# 7_VGA.net
KiCad netlist of a schematic drawn in Altium Designer
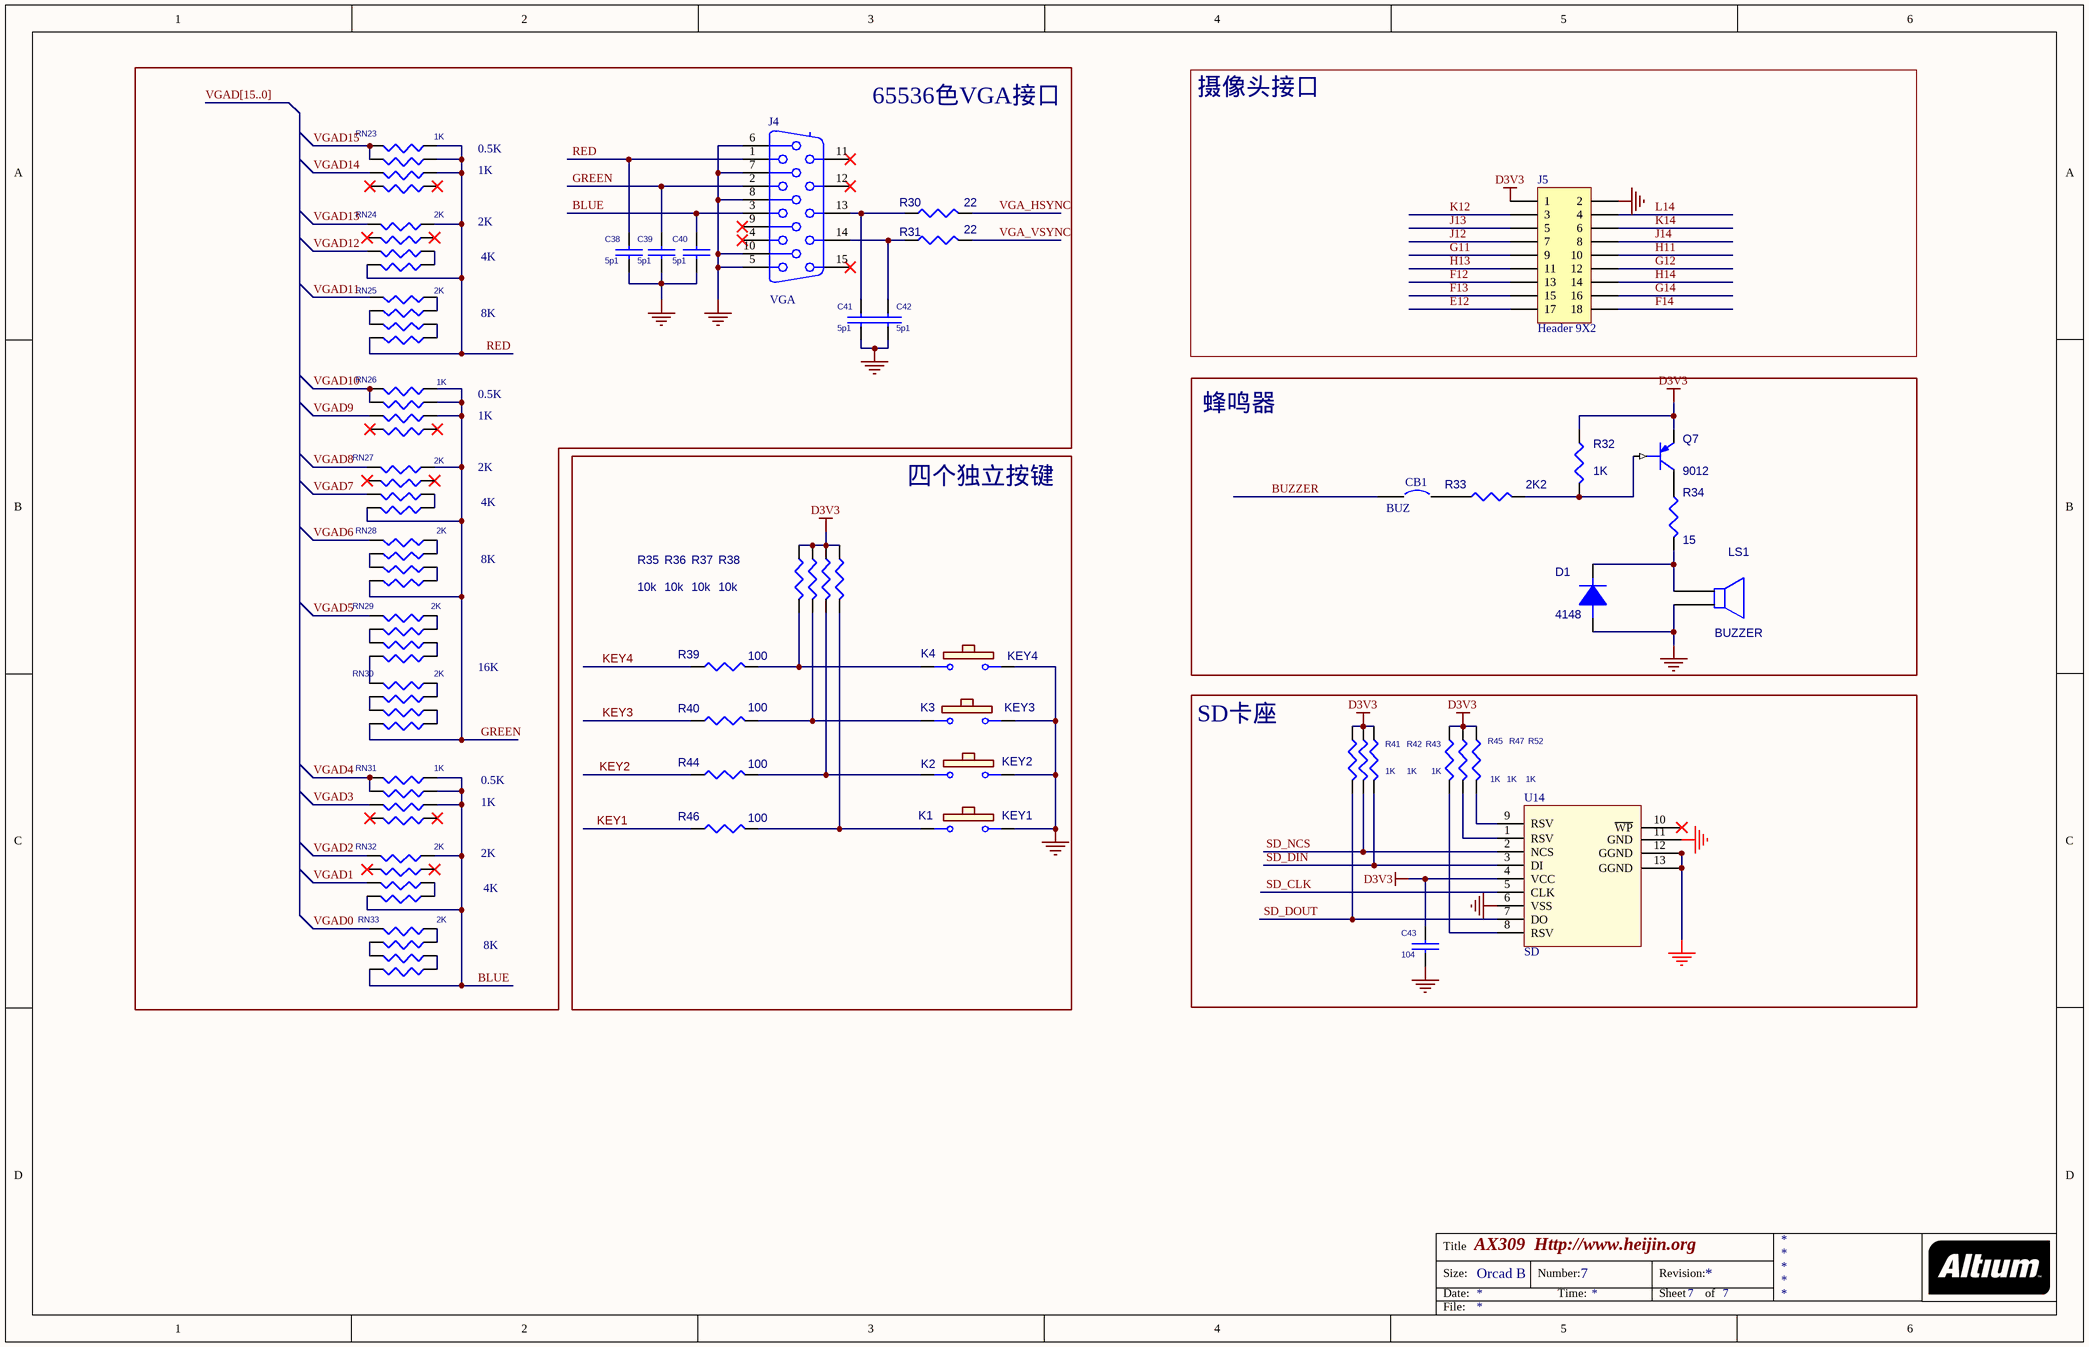
[diagram p0: 7_VGA.SchDoc]

(export (version "E")
  (design (tool "Eeschema 10.0.6"))
  (components
    (comp (ref "C38") (value "5p1") (footprint "0603") (libsource (lib "*") (part "C_Dup1")))
    (comp (ref "C39") (value "5p1") (footprint "0603") (libsource (lib "*") (part "C_Dup1")))
    (comp (ref "C40") (value "5p1") (footprint "0603") (libsource (lib "*") (part "C_Dup1")))
    (comp (ref "C41") (value "5p1") (footprint "0603") (libsource (lib "*") (part "C_Dup1")))
    (comp (ref "C42") (value "5p1") (footprint "0603") (libsource (lib "*") (part "C_Dup1")))
    (comp (ref "C43") (value "104") (footprint "0402") (libsource (lib "*") (part "C_Dup1")))
    (comp (ref "CB1")
      (value "BUZ")
      (footprint "SIP2")
      (description "Circuit Breaker")
      (fields (field (name "PUBLISHER") "Altium Limited"))
      (libsource (lib "Miscellaneous Devices") (part "Circuit Breaker"))
    )
    (comp (ref "D1") (value "4148") (libsource (lib "*") (part "4148")))
    (comp (ref "J4")
      (value "VGA")
      (footprint "wfj_pcb:VGA")
      (description "Receptacle Assembly, 15-Pin, Sim Line Connector")
      (fields (field (name "PUBLISHER") "Altium Limited"))
      (libsource (lib "Miscellaneous Connectors") (part "Connector 15"))
    )
    (comp (ref "J5")
      (value "Header 9X2")
      (footprint "HDR2X9")
      (description "Header, 9-Pin, Dual row")
      (fields (field (name "PUBLISHER") "Altium Limited"))
      (libsource (lib "Miscellaneous Connectors") (part "Header 9X2"))
    )
    (comp (ref "K1") (value "KEY1") (footprint "KEY735SO") (libsource (lib "*") (part "KEYB")))
    (comp (ref "K2") (value "KEY2") (footprint "KEY735SO") (libsource (lib "*") (part "KEYB")))
    (comp (ref "K3") (value "KEY3") (footprint "KEY735SO") (libsource (lib "") (part "KEYB_1")))
    (comp (ref "K4") (value "KEY4") (footprint "KEY735SO") (libsource (lib "*") (part "KEYB")))
    (comp (ref "LS1") (value "BUZZER") (libsource (lib "*") (part "SPEAKER")))
    (comp (ref "Q7") (value "9012") (footprint "SOT23") (libsource (lib "*") (part "PNP")))
    (comp (ref "R30") (value "22") (footprint "0603") (libsource (lib "*") (part "R")))
    (comp (ref "R31") (value "22") (footprint "0603") (libsource (lib "*") (part "R")))
    (comp (ref "R32") (value "1K") (footprint "0603") (libsource (lib "*") (part "R_Dup3")))
    (comp (ref "R33") (value "2K2") (footprint "0603") (libsource (lib "*") (part "R_Dup3")))
    (comp (ref "R34") (value "15") (footprint "0603") (libsource (lib "*") (part "R_Dup3")))
    (comp (ref "R35") (value "10k") (footprint "0603") (libsource (lib "*") (part "R_Dup2")))
    (comp (ref "R36") (value "10k") (footprint "0603") (libsource (lib "*") (part "R_Dup2")))
    (comp (ref "R37") (value "10k") (footprint "0603") (libsource (lib "*") (part "R_Dup2")))
    (comp (ref "R38") (value "10k") (footprint "0603") (libsource (lib "*") (part "R_Dup2")))
    (comp (ref "R39") (value "100") (footprint "0603") (libsource (lib "*") (part "R_Dup2")))
    (comp (ref "R40") (value "100") (footprint "0603") (libsource (lib "*") (part "R_Dup2")))
    (comp (ref "R41") (value "1K") (footprint "0603") (libsource (lib "*") (part "R")))
    (comp (ref "R42") (value "1K") (footprint "0603") (libsource (lib "*") (part "R")))
    (comp (ref "R43") (value "1K") (footprint "0603") (libsource (lib "*") (part "R")))
    (comp (ref "R44") (value "100") (footprint "0603") (libsource (lib "*") (part "R_Dup2")))
    (comp (ref "R45") (value "1K") (footprint "0603") (libsource (lib "*") (part "R")))
    (comp (ref "R46") (value "100") (footprint "0603") (libsource (lib "*") (part "R_Dup2")))
    (comp (ref "R47") (value "1K") (footprint "0603") (libsource (lib "*") (part "R")))
    (comp (ref "R52") (value "1K") (footprint "0603") (libsource (lib "*") (part "R")))
    (comp (ref "RN23") (value "1K") (footprint "RN-8P") (libsource (lib "*") (part "RN_Dup1")))
    (comp (ref "RN24") (value "2K") (footprint "RN-8P") (libsource (lib "*") (part "RN_Dup1")))
    (comp (ref "RN25") (value "2K") (footprint "RN-8P") (libsource (lib "*") (part "RN_Dup1")))
    (comp (ref "RN26") (value "1K") (footprint "RN-8P") (libsource (lib "*") (part "RN_Dup1")))
    (comp (ref "RN27") (value "2K") (footprint "RN-8P") (libsource (lib "*") (part "RN_Dup1")))
    (comp (ref "RN28") (value "2K") (footprint "RN-8P") (libsource (lib "*") (part "RN_Dup1")))
    (comp (ref "RN29") (value "2K") (footprint "RN-8P") (libsource (lib "*") (part "RN_Dup1")))
    (comp (ref "RN30") (value "2K") (footprint "RN-8P") (libsource (lib "*") (part "RN_Dup1")))
    (comp (ref "RN31") (value "1K") (footprint "RN-8P") (libsource (lib "*") (part "RN_Dup1")))
    (comp (ref "RN32") (value "2K") (footprint "RN-8P") (libsource (lib "*") (part "RN_Dup1")))
    (comp (ref "RN33") (value "2K") (footprint "RN-8P") (libsource (lib "*") (part "RN_Dup1")))
    (comp (ref "U14") (value "SD") (footprint "TF") (libsource (lib "TFT") (part "SD")))
  )
  (nets
    (net (code "1") (name "/BLUE") (class "Default")
      (node (ref "C40") (pin "1") (pinfunction "1_1") (pintype "passive"))
      (node (ref "J4") (pin "3") (pinfunction "3_3") (pintype "passive"))
      (node (ref "RN31") (pin "2") (pinfunction "2_2") (pintype "passive"))
      (node (ref "RN31") (pin "3") (pinfunction "3_3") (pintype "passive"))
      (node (ref "RN31") (pin "4") (pinfunction "4_4") (pintype "passive"))
      (node (ref "RN32") (pin "4") (pinfunction "4_4") (pintype "passive"))
      (node (ref "RN32") (pin "8") (pinfunction "8_8") (pintype "passive"))
      (node (ref "RN33") (pin "8") (pinfunction "8_8") (pintype "passive"))
    )
    (net (code "2") (name "/BUZZER") (class "Default")
      (node (ref "CB1") (pin "1") (pinfunction "1_1") (pintype "passive"))
    )
    (net (code "3") (name "/E12") (class "Default")
      (node (ref "J5") (pin "17") (pinfunction "17_17") (pintype "passive"))
    )
    (net (code "4") (name "/F12") (class "Default")
      (node (ref "J5") (pin "13") (pinfunction "13_13") (pintype "passive"))
    )
    (net (code "5") (name "/F13") (class "Default")
      (node (ref "J5") (pin "15") (pinfunction "15_15") (pintype "passive"))
    )
    (net (code "6") (name "/F14") (class "Default")
      (node (ref "J5") (pin "18") (pinfunction "18_18") (pintype "passive"))
    )
    (net (code "7") (name "/G11") (class "Default")
      (node (ref "J5") (pin "9") (pinfunction "9_9") (pintype "passive"))
    )
    (net (code "8") (name "/G12") (class "Default")
      (node (ref "J5") (pin "12") (pinfunction "12_12") (pintype "passive"))
    )
    (net (code "9") (name "/G14") (class "Default")
      (node (ref "J5") (pin "16") (pinfunction "16_16") (pintype "passive"))
    )
    (net (code "10") (name "/GREEN") (class "Default")
      (node (ref "C39") (pin "1") (pinfunction "1_1") (pintype "passive"))
      (node (ref "J4") (pin "2") (pinfunction "2_2") (pintype "passive"))
      (node (ref "RN26") (pin "2") (pinfunction "2_2") (pintype "passive"))
      (node (ref "RN26") (pin "3") (pinfunction "3_3") (pintype "passive"))
      (node (ref "RN26") (pin "4") (pinfunction "4_4") (pintype "passive"))
      (node (ref "RN27") (pin "4") (pinfunction "4_4") (pintype "passive"))
      (node (ref "RN27") (pin "8") (pinfunction "8_8") (pintype "passive"))
      (node (ref "RN28") (pin "8") (pinfunction "8_8") (pintype "passive"))
      (node (ref "RN30") (pin "8") (pinfunction "8_8") (pintype "passive"))
    )
    (net (code "11") (name "/H11") (class "Default")
      (node (ref "J5") (pin "10") (pinfunction "10_10") (pintype "passive"))
    )
    (net (code "12") (name "/H13") (class "Default")
      (node (ref "J5") (pin "11") (pinfunction "11_11") (pintype "passive"))
    )
    (net (code "13") (name "/H14") (class "Default")
      (node (ref "J5") (pin "14") (pinfunction "14_14") (pintype "passive"))
    )
    (net (code "14") (name "/J12") (class "Default")
      (node (ref "J5") (pin "7") (pinfunction "7_7") (pintype "passive"))
    )
    (net (code "15") (name "/J13") (class "Default")
      (node (ref "J5") (pin "5") (pinfunction "5_5") (pintype "passive"))
    )
    (net (code "16") (name "/J14") (class "Default")
      (node (ref "J5") (pin "8") (pinfunction "8_8") (pintype "passive"))
    )
    (net (code "17") (name "/K12") (class "Default")
      (node (ref "J5") (pin "3") (pinfunction "3_3") (pintype "passive"))
    )
    (net (code "18") (name "/K14") (class "Default")
      (node (ref "J5") (pin "6") (pinfunction "6_6") (pintype "passive"))
    )
    (net (code "19") (name "/KEY1") (class "Default")
      (node (ref "R46") (pin "1") (pinfunction "1_1") (pintype "passive"))
    )
    (net (code "20") (name "/KEY2") (class "Default")
      (node (ref "R44") (pin "1") (pinfunction "1_1") (pintype "passive"))
    )
    (net (code "21") (name "/KEY3") (class "Default")
      (node (ref "R40") (pin "1") (pinfunction "1_1") (pintype "passive"))
    )
    (net (code "22") (name "/KEY4") (class "Default")
      (node (ref "R39") (pin "1") (pinfunction "1_1") (pintype "passive"))
    )
    (net (code "23") (name "/L14") (class "Default")
      (node (ref "J5") (pin "4") (pinfunction "4_4") (pintype "passive"))
    )
    (net (code "24") (name "/RED") (class "Default")
      (node (ref "C38") (pin "1") (pinfunction "1_1") (pintype "passive"))
      (node (ref "J4") (pin "1") (pinfunction "1_1") (pintype "passive"))
      (node (ref "RN23") (pin "2") (pinfunction "2_2") (pintype "passive"))
      (node (ref "RN23") (pin "3") (pinfunction "3_3") (pintype "passive"))
      (node (ref "RN23") (pin "4") (pinfunction "4_4") (pintype "passive"))
      (node (ref "RN24") (pin "4") (pinfunction "4_4") (pintype "passive"))
      (node (ref "RN24") (pin "8") (pinfunction "8_8") (pintype "passive"))
      (node (ref "RN25") (pin "8") (pinfunction "8_8") (pintype "passive"))
    )
    (net (code "25") (name "/SD_CLK") (class "Default")
      (node (ref "U14") (pin "5") (pinfunction "CLK_5") (pintype "passive"))
    )
    (net (code "26") (name "/SD_DIN") (class "Default")
      (node (ref "R43") (pin "2") (pinfunction "2_2") (pintype "passive"))
      (node (ref "U14") (pin "3") (pinfunction "DI_3") (pintype "passive"))
    )
    (net (code "27") (name "/SD_DOUT") (class "Default")
      (node (ref "R41") (pin "2") (pinfunction "2_2") (pintype "passive"))
      (node (ref "U14") (pin "7") (pinfunction "DO_7") (pintype "passive"))
    )
    (net (code "28") (name "/SD_NCS") (class "Default")
      (node (ref "R42") (pin "2") (pinfunction "2_2") (pintype "passive"))
      (node (ref "U14") (pin "2") (pinfunction "NCS_2") (pintype "passive"))
    )
    (net (code "29") (name "/VGAD0") (class "Default")
      (node (ref "RN33") (pin "5") (pinfunction "5_5") (pintype "passive"))
    )
    (net (code "30") (name "/VGAD1") (class "Default")
      (node (ref "RN32") (pin "7") (pinfunction "7_7") (pintype "passive"))
    )
    (net (code "31") (name "/VGAD2") (class "Default")
      (node (ref "RN32") (pin "5") (pinfunction "5_5") (pintype "passive"))
    )
    (net (code "32") (name "/VGAD3") (class "Default")
      (node (ref "RN31") (pin "7") (pinfunction "7_7") (pintype "passive"))
    )
    (net (code "33") (name "/VGAD4") (class "Default")
      (node (ref "RN31") (pin "5") (pinfunction "5_5") (pintype "passive"))
      (node (ref "RN31") (pin "6") (pinfunction "6_6") (pintype "passive"))
    )
    (net (code "34") (name "/VGAD5") (class "Default")
      (node (ref "RN29") (pin "5") (pinfunction "5_5") (pintype "passive"))
    )
    (net (code "35") (name "/VGAD6") (class "Default")
      (node (ref "RN28") (pin "5") (pinfunction "5_5") (pintype "passive"))
    )
    (net (code "36") (name "/VGAD7") (class "Default")
      (node (ref "RN27") (pin "7") (pinfunction "7_7") (pintype "passive"))
    )
    (net (code "37") (name "/VGAD8") (class "Default")
      (node (ref "RN27") (pin "5") (pinfunction "5_5") (pintype "passive"))
    )
    (net (code "38") (name "/VGAD9") (class "Default")
      (node (ref "RN26") (pin "7") (pinfunction "7_7") (pintype "passive"))
    )
    (net (code "39") (name "/VGAD10") (class "Default")
      (node (ref "RN26") (pin "5") (pinfunction "5_5") (pintype "passive"))
      (node (ref "RN26") (pin "6") (pinfunction "6_6") (pintype "passive"))
    )
    (net (code "40") (name "/VGAD11") (class "Default")
      (node (ref "RN25") (pin "5") (pinfunction "5_5") (pintype "passive"))
    )
    (net (code "41") (name "/VGAD12") (class "Default")
      (node (ref "RN24") (pin "7") (pinfunction "7_7") (pintype "passive"))
    )
    (net (code "42") (name "/VGAD13") (class "Default")
      (node (ref "RN24") (pin "5") (pinfunction "5_5") (pintype "passive"))
    )
    (net (code "43") (name "/VGAD14") (class "Default")
      (node (ref "RN23") (pin "7") (pinfunction "7_7") (pintype "passive"))
    )
    (net (code "44") (name "/VGAD15") (class "Default")
      (node (ref "RN23") (pin "5") (pinfunction "5_5") (pintype "passive"))
      (node (ref "RN23") (pin "6") (pinfunction "6_6") (pintype "passive"))
    )
    (net (code "46") (name "/VGA_HSYNC") (class "Default")
      (node (ref "R30") (pin "2") (pinfunction "2_2") (pintype "passive"))
    )
    (net (code "47") (name "/VGA_VSYNC") (class "Default")
      (node (ref "R31") (pin "2") (pinfunction "2_2") (pintype "passive"))
    )
    (net (code "48") (name "D3V3") (class "Default")
      (node (ref "C43") (pin "1") (pinfunction "1_1") (pintype "passive"))
      (node (ref "J5") (pin "1") (pinfunction "1_1") (pintype "passive"))
      (node (ref "Q7") (pin "2") (pinfunction "EMITTER_2") (pintype "passive"))
      (node (ref "R32") (pin "1") (pinfunction "1_1") (pintype "passive"))
      (node (ref "R35") (pin "1") (pinfunction "1_1") (pintype "passive"))
      (node (ref "R36") (pin "1") (pinfunction "1_1") (pintype "passive"))
      (node (ref "R37") (pin "1") (pinfunction "1_1") (pintype "passive"))
      (node (ref "R38") (pin "1") (pinfunction "1_1") (pintype "passive"))
      (node (ref "R41") (pin "1") (pinfunction "1_1") (pintype "passive"))
      (node (ref "R42") (pin "1") (pinfunction "1_1") (pintype "passive"))
      (node (ref "R43") (pin "1") (pinfunction "1_1") (pintype "passive"))
      (node (ref "R45") (pin "1") (pinfunction "1_1") (pintype "passive"))
      (node (ref "R47") (pin "1") (pinfunction "1_1") (pintype "passive"))
      (node (ref "R52") (pin "1") (pinfunction "1_1") (pintype "passive"))
      (node (ref "U14") (pin "4") (pinfunction "VCC_4") (pintype "passive"))
    )
    (net (code "49") (name "GND") (class "Default")
      (node (ref "C38") (pin "2") (pinfunction "2_2") (pintype "passive"))
      (node (ref "C39") (pin "2") (pinfunction "2_2") (pintype "passive"))
      (node (ref "C40") (pin "2") (pinfunction "2_2") (pintype "passive"))
      (node (ref "C41") (pin "2") (pinfunction "2_2") (pintype "passive"))
      (node (ref "C42") (pin "2") (pinfunction "2_2") (pintype "passive"))
      (node (ref "C43") (pin "2") (pinfunction "2_2") (pintype "passive"))
      (node (ref "D1") (pin "1") (pinfunction "A_1") (pintype "passive"))
      (node (ref "J4") (pin "10") (pinfunction "10_10") (pintype "passive"))
      (node (ref "J4") (pin "5") (pinfunction "5_5") (pintype "passive"))
      (node (ref "J4") (pin "6") (pinfunction "6_6") (pintype "passive"))
      (node (ref "J4") (pin "7") (pinfunction "7_7") (pintype "passive"))
      (node (ref "J4") (pin "8") (pinfunction "8_8") (pintype "passive"))
      (node (ref "J5") (pin "2") (pinfunction "2_2") (pintype "passive"))
      (node (ref "K1") (pin "2") (pinfunction "2_2") (pintype "passive"))
      (node (ref "K2") (pin "2") (pinfunction "2_2") (pintype "passive"))
      (node (ref "K3") (pin "1") (pinfunction "1_1") (pintype "passive"))
      (node (ref "K4") (pin "2") (pinfunction "2_2") (pintype "passive"))
      (node (ref "LS1") (pin "2") (pinfunction "2_2") (pintype "passive"))
      (node (ref "U14") (pin "11") (pinfunction "GND_11") (pintype "passive"))
      (node (ref "U14") (pin "12") (pinfunction "GGND_12") (pintype "passive"))
      (node (ref "U14") (pin "13") (pinfunction "GGND_13") (pintype "passive"))
      (node (ref "U14") (pin "6") (pinfunction "VSS_6") (pintype "passive"))
    )
    (net (code "50") (name "Net-(C41-Pad1)") (class "Default")
      (node (ref "C41") (pin "1") (pinfunction "1_1") (pintype "passive"))
      (node (ref "J4") (pin "13") (pinfunction "13_13") (pintype "passive"))
      (node (ref "R30") (pin "1") (pinfunction "1_1") (pintype "passive"))
    )
    (net (code "51") (name "Net-(C42-Pad1)") (class "Default")
      (node (ref "C42") (pin "1") (pinfunction "1_1") (pintype "passive"))
      (node (ref "J4") (pin "14") (pinfunction "14_14") (pintype "passive"))
      (node (ref "R31") (pin "1") (pinfunction "1_1") (pintype "passive"))
    )
    (net (code "52") (name "Net-(CB1-Pad2)") (class "Default")
      (node (ref "CB1") (pin "2") (pinfunction "2_2") (pintype "passive"))
      (node (ref "R33") (pin "1") (pinfunction "1_1") (pintype "passive"))
    )
    (net (code "53") (name "Net-(D1-C)") (class "Default")
      (node (ref "D1") (pin "2") (pinfunction "C_2") (pintype "passive"))
      (node (ref "LS1") (pin "1") (pinfunction "1_1") (pintype "passive"))
      (node (ref "R34") (pin "2") (pinfunction "2_2") (pintype "passive"))
    )
    (net (code "54") (name "Net-(K1-Pad1)") (class "Default")
      (node (ref "K1") (pin "1") (pinfunction "1_1") (pintype "passive"))
      (node (ref "R38") (pin "2") (pinfunction "2_2") (pintype "passive"))
      (node (ref "R46") (pin "2") (pinfunction "2_2") (pintype "passive"))
    )
    (net (code "55") (name "Net-(K2-Pad1)") (class "Default")
      (node (ref "K2") (pin "1") (pinfunction "1_1") (pintype "passive"))
      (node (ref "R37") (pin "2") (pinfunction "2_2") (pintype "passive"))
      (node (ref "R44") (pin "2") (pinfunction "2_2") (pintype "passive"))
    )
    (net (code "56") (name "Net-(K3-Pad2)") (class "Default")
      (node (ref "K3") (pin "2") (pinfunction "2_2") (pintype "passive"))
      (node (ref "R36") (pin "2") (pinfunction "2_2") (pintype "passive"))
      (node (ref "R40") (pin "2") (pinfunction "2_2") (pintype "passive"))
    )
    (net (code "57") (name "Net-(K4-Pad1)") (class "Default")
      (node (ref "K4") (pin "1") (pinfunction "1_1") (pintype "passive"))
      (node (ref "R35") (pin "2") (pinfunction "2_2") (pintype "passive"))
      (node (ref "R39") (pin "2") (pinfunction "2_2") (pintype "passive"))
    )
    (net (code "58") (name "Net-(Q7-BASE)") (class "Default")
      (node (ref "Q7") (pin "1") (pinfunction "BASE_1") (pintype "input"))
      (node (ref "R32") (pin "2") (pinfunction "2_2") (pintype "passive"))
      (node (ref "R33") (pin "2") (pinfunction "2_2") (pintype "passive"))
    )
    (net (code "59") (name "Net-(Q7-COLLECTOR)") (class "Default")
      (node (ref "Q7") (pin "3") (pinfunction "COLLECTOR_3") (pintype "passive"))
      (node (ref "R34") (pin "1") (pinfunction "1_1") (pintype "passive"))
    )
    (net (code "60") (name "Net-(R45-Pad2)") (class "Default")
      (node (ref "R45") (pin "2") (pinfunction "2_2") (pintype "passive"))
      (node (ref "U14") (pin "8") (pinfunction "RSV_8") (pintype "passive"))
    )
    (net (code "61") (name "Net-(R47-Pad2)") (class "Default")
      (node (ref "R47") (pin "2") (pinfunction "2_2") (pintype "passive"))
      (node (ref "U14") (pin "1") (pinfunction "RSV_1") (pintype "passive"))
    )
    (net (code "62") (name "Net-(R52-Pad2)") (class "Default")
      (node (ref "R52") (pin "2") (pinfunction "2_2") (pintype "passive"))
      (node (ref "U14") (pin "9") (pinfunction "RSV_9") (pintype "passive"))
    )
    (net (code "63") (name "Net-(RN24-Pad1)") (class "Default")
      (node (ref "RN24") (pin "1") (pinfunction "1_1") (pintype "passive"))
      (node (ref "RN24") (pin "2") (pinfunction "2_2") (pintype "passive"))
    )
    (net (code "64") (name "Net-(RN25-Pad1)") (class "Default")
      (node (ref "RN25") (pin "1") (pinfunction "1_1") (pintype "passive"))
      (node (ref "RN25") (pin "2") (pinfunction "2_2") (pintype "passive"))
    )
    (net (code "65") (name "Net-(RN25-Pad3)") (class "Default")
      (node (ref "RN25") (pin "3") (pinfunction "3_3") (pintype "passive"))
      (node (ref "RN25") (pin "4") (pinfunction "4_4") (pintype "passive"))
    )
    (net (code "66") (name "Net-(RN25-Pad6)") (class "Default")
      (node (ref "RN25") (pin "6") (pinfunction "6_6") (pintype "passive"))
      (node (ref "RN25") (pin "7") (pinfunction "7_7") (pintype "passive"))
    )
    (net (code "67") (name "Net-(RN27-Pad1)") (class "Default")
      (node (ref "RN27") (pin "1") (pinfunction "1_1") (pintype "passive"))
      (node (ref "RN27") (pin "2") (pinfunction "2_2") (pintype "passive"))
    )
    (net (code "68") (name "Net-(RN28-Pad1)") (class "Default")
      (node (ref "RN28") (pin "1") (pinfunction "1_1") (pintype "passive"))
      (node (ref "RN28") (pin "2") (pinfunction "2_2") (pintype "passive"))
    )
    (net (code "69") (name "Net-(RN28-Pad3)") (class "Default")
      (node (ref "RN28") (pin "3") (pinfunction "3_3") (pintype "passive"))
      (node (ref "RN28") (pin "4") (pinfunction "4_4") (pintype "passive"))
    )
    (net (code "70") (name "Net-(RN28-Pad6)") (class "Default")
      (node (ref "RN28") (pin "6") (pinfunction "6_6") (pintype "passive"))
      (node (ref "RN28") (pin "7") (pinfunction "7_7") (pintype "passive"))
    )
    (net (code "71") (name "Net-(RN29-Pad1)") (class "Default")
      (node (ref "RN29") (pin "1") (pinfunction "1_1") (pintype "passive"))
      (node (ref "RN29") (pin "2") (pinfunction "2_2") (pintype "passive"))
    )
    (net (code "72") (name "Net-(RN29-Pad3)") (class "Default")
      (node (ref "RN29") (pin "3") (pinfunction "3_3") (pintype "passive"))
      (node (ref "RN29") (pin "4") (pinfunction "4_4") (pintype "passive"))
    )
    (net (code "73") (name "Net-(RN29-Pad6)") (class "Default")
      (node (ref "RN29") (pin "6") (pinfunction "6_6") (pintype "passive"))
      (node (ref "RN29") (pin "7") (pinfunction "7_7") (pintype "passive"))
    )
    (net (code "74") (name "Net-(RN29-Pad8)") (class "Default")
      (node (ref "RN29") (pin "8") (pinfunction "8_8") (pintype "passive"))
      (node (ref "RN30") (pin "5") (pinfunction "5_5") (pintype "passive"))
    )
    (net (code "75") (name "Net-(RN30-Pad1)") (class "Default")
      (node (ref "RN30") (pin "1") (pinfunction "1_1") (pintype "passive"))
      (node (ref "RN30") (pin "2") (pinfunction "2_2") (pintype "passive"))
    )
    (net (code "76") (name "Net-(RN30-Pad3)") (class "Default")
      (node (ref "RN30") (pin "3") (pinfunction "3_3") (pintype "passive"))
      (node (ref "RN30") (pin "4") (pinfunction "4_4") (pintype "passive"))
    )
    (net (code "77") (name "Net-(RN30-Pad6)") (class "Default")
      (node (ref "RN30") (pin "6") (pinfunction "6_6") (pintype "passive"))
      (node (ref "RN30") (pin "7") (pinfunction "7_7") (pintype "passive"))
    )
    (net (code "78") (name "Net-(RN32-Pad1)") (class "Default")
      (node (ref "RN32") (pin "1") (pinfunction "1_1") (pintype "passive"))
      (node (ref "RN32") (pin "2") (pinfunction "2_2") (pintype "passive"))
    )
    (net (code "79") (name "Net-(RN33-Pad1)") (class "Default")
      (node (ref "RN33") (pin "1") (pinfunction "1_1") (pintype "passive"))
      (node (ref "RN33") (pin "2") (pinfunction "2_2") (pintype "passive"))
    )
    (net (code "80") (name "Net-(RN33-Pad3)") (class "Default")
      (node (ref "RN33") (pin "3") (pinfunction "3_3") (pintype "passive"))
      (node (ref "RN33") (pin "4") (pinfunction "4_4") (pintype "passive"))
    )
    (net (code "81") (name "Net-(RN33-Pad6)") (class "Default")
      (node (ref "RN33") (pin "6") (pinfunction "6_6") (pintype "passive"))
      (node (ref "RN33") (pin "7") (pinfunction "7_7") (pintype "passive"))
    )
    (net (code "82") (name "unconnected-(J4-MH1-Pad16)") (class "Default")
      (node (ref "J4") (pin "16") (pinfunction "MH1_16") (pintype "passive"))
    )
    (net (code "83") (name "unconnected-(J4-MH2-Pad17)") (class "Default")
      (node (ref "J4") (pin "17") (pinfunction "MH2_17") (pintype "passive"))
    )
    (net (code "84") (name "unconnected-(J4-Pad4)") (class "Default")
      (node (ref "J4") (pin "4") (pinfunction "4_4") (pintype "passive+no_connect"))
    )
    (net (code "85") (name "unconnected-(J4-Pad9)") (class "Default")
      (node (ref "J4") (pin "9") (pinfunction "9_9") (pintype "passive+no_connect"))
    )
    (net (code "86") (name "unconnected-(J4-Pad11)") (class "Default")
      (node (ref "J4") (pin "11") (pinfunction "11_11") (pintype "passive+no_connect"))
    )
    (net (code "87") (name "unconnected-(J4-Pad12)") (class "Default")
      (node (ref "J4") (pin "12") (pinfunction "12_12") (pintype "passive+no_connect"))
    )
    (net (code "88") (name "unconnected-(J4-Pad15)") (class "Default")
      (node (ref "J4") (pin "15") (pinfunction "15_15") (pintype "passive+no_connect"))
    )
    (net (code "89") (name "unconnected-(RN23-Pad1)") (class "Default")
      (node (ref "RN23") (pin "1") (pinfunction "1_1") (pintype "passive+no_connect"))
    )
    (net (code "90") (name "unconnected-(RN23-Pad8)") (class "Default")
      (node (ref "RN23") (pin "8") (pinfunction "8_8") (pintype "passive+no_connect"))
    )
    (net (code "91") (name "unconnected-(RN24-Pad3)") (class "Default")
      (node (ref "RN24") (pin "3") (pinfunction "3_3") (pintype "passive+no_connect"))
    )
    (net (code "92") (name "unconnected-(RN24-Pad6)") (class "Default")
      (node (ref "RN24") (pin "6") (pinfunction "6_6") (pintype "passive+no_connect"))
    )
    (net (code "93") (name "unconnected-(RN26-Pad1)") (class "Default")
      (node (ref "RN26") (pin "1") (pinfunction "1_1") (pintype "passive+no_connect"))
    )
    (net (code "94") (name "unconnected-(RN26-Pad8)") (class "Default")
      (node (ref "RN26") (pin "8") (pinfunction "8_8") (pintype "passive+no_connect"))
    )
    (net (code "95") (name "unconnected-(RN27-Pad3)") (class "Default")
      (node (ref "RN27") (pin "3") (pinfunction "3_3") (pintype "passive+no_connect"))
    )
    (net (code "96") (name "unconnected-(RN27-Pad6)") (class "Default")
      (node (ref "RN27") (pin "6") (pinfunction "6_6") (pintype "passive+no_connect"))
    )
    (net (code "97") (name "unconnected-(RN31-Pad1)") (class "Default")
      (node (ref "RN31") (pin "1") (pinfunction "1_1") (pintype "passive+no_connect"))
    )
    (net (code "98") (name "unconnected-(RN31-Pad8)") (class "Default")
      (node (ref "RN31") (pin "8") (pinfunction "8_8") (pintype "passive+no_connect"))
    )
    (net (code "99") (name "unconnected-(RN32-Pad3)") (class "Default")
      (node (ref "RN32") (pin "3") (pinfunction "3_3") (pintype "passive+no_connect"))
    )
    (net (code "100") (name "unconnected-(RN32-Pad6)") (class "Default")
      (node (ref "RN32") (pin "6") (pinfunction "6_6") (pintype "passive+no_connect"))
    )
    (net (code "101") (name "unconnected-(U14-~{WP}-Pad10)") (class "Default")
      (node (ref "U14") (pin "10") (pinfunction "~{WP}_10") (pintype "passive+no_connect"))
    )
  )
)
